# Logic_Engine_-_AVR.net
KiCad netlist of a schematic drawn in EAGLE
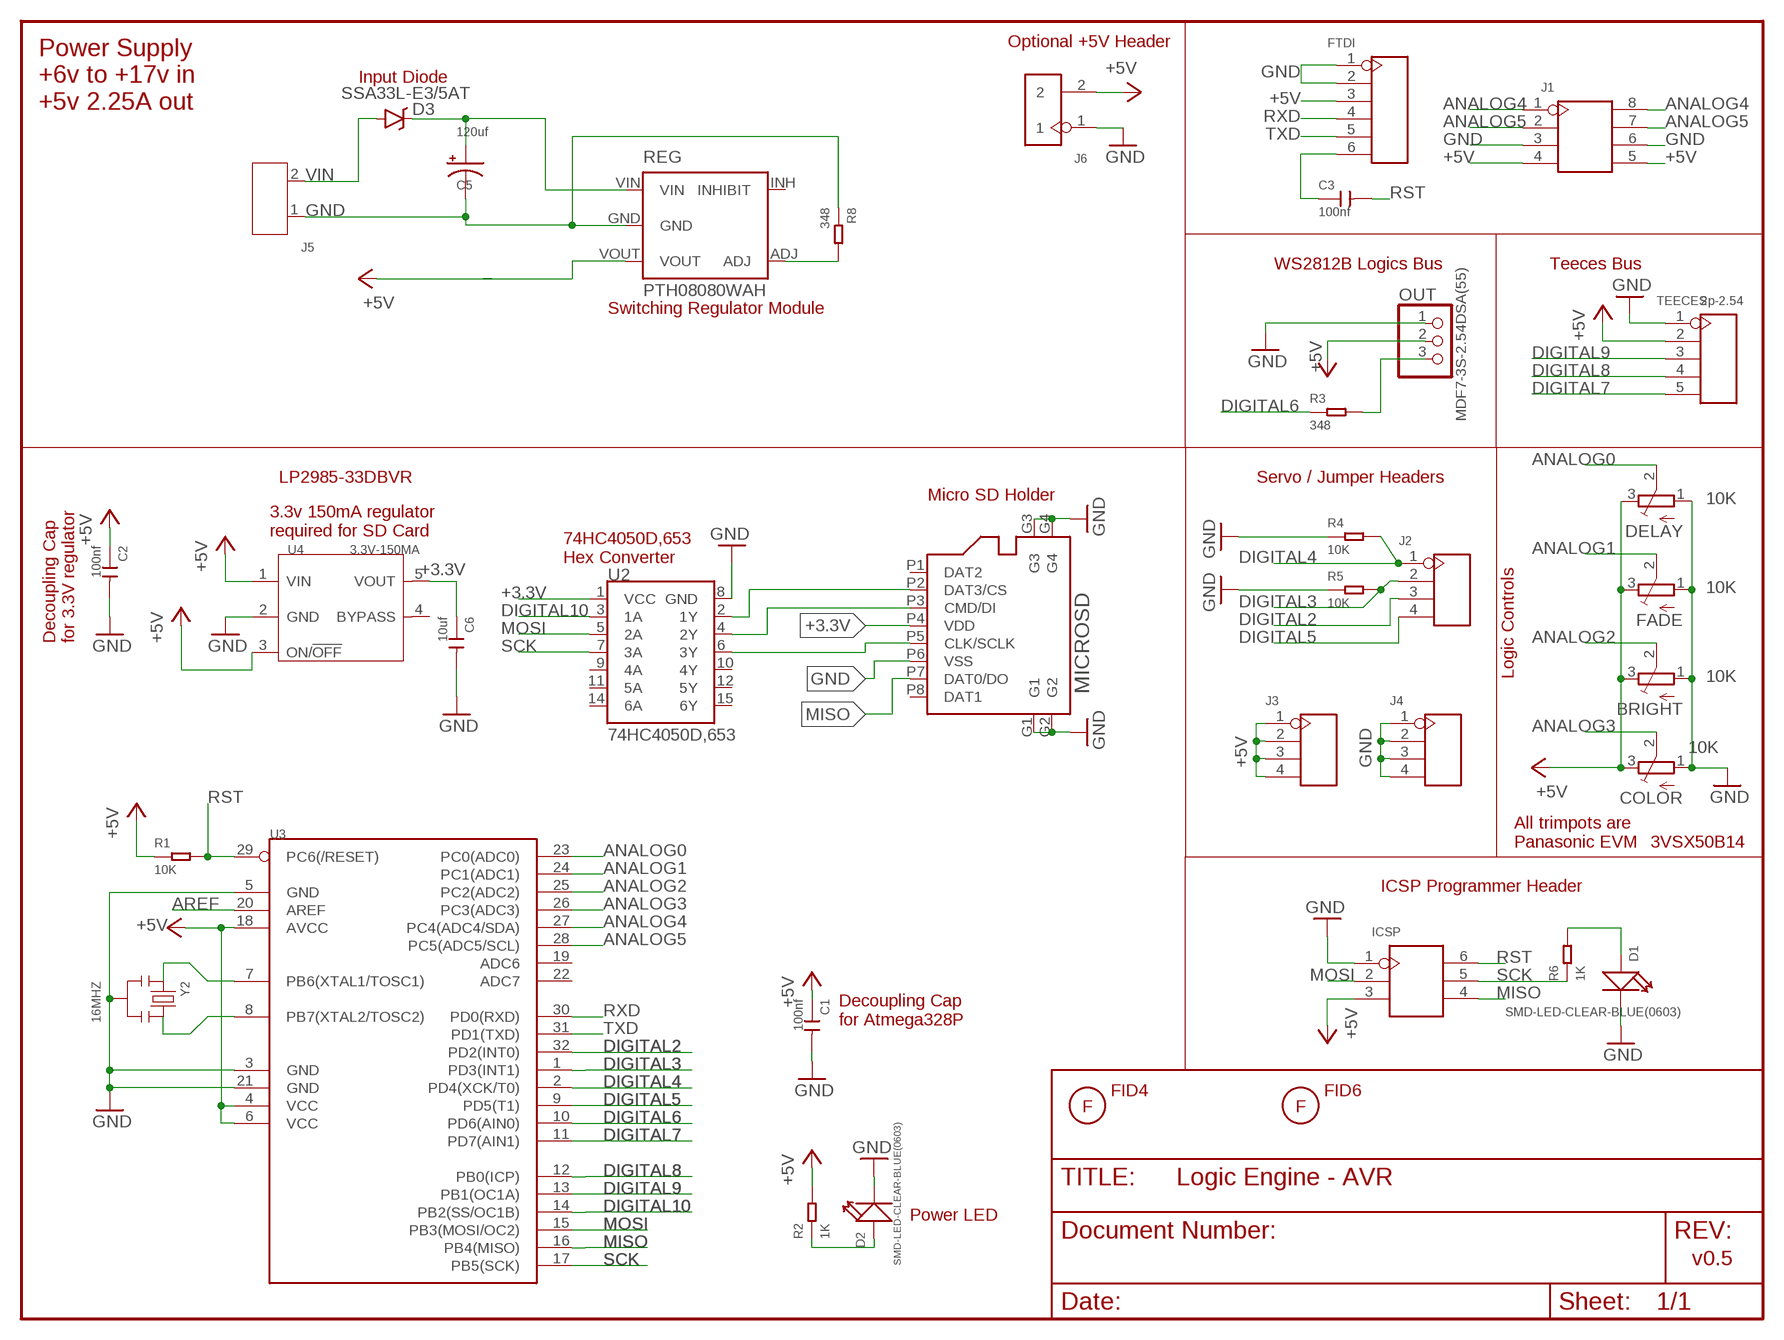
[diagram p0: schematic, sheet 1]

(export (version "E")
  (design (tool "Eeschema 10.0.6"))
  (components
    (comp (ref "BRIGHT")
      (value "10K")
      (footprint "eagle-import:EVM3V")
      (libsource (lib "eagle-import") (part "TRIMPOTEVM3V"))
    )
    (comp (ref "C1")
      (value "100nf")
      (footprint "eagle-import:C0805")
      (fields (field (name "MPN") "CC0805KRX7R9BB104"))
      (libsource (lib "eagle-import") (part "CERAMIC-100NF-50V-10%-X7R(0805)"))
    )
    (comp (ref "C2")
      (value "100nf")
      (footprint "eagle-import:C0805")
      (fields (field (name "MPN") "CC0805KRX7R9BB104"))
      (libsource (lib "eagle-import") (part "CERAMIC-100NF-50V-10%-X7R(0805)"))
    )
    (comp (ref "C3")
      (value "100nf")
      (footprint "eagle-import:C0805")
      (fields (field (name "MPN") "CC0805KRX7R9BB104"))
      (libsource (lib "eagle-import") (part "CERAMIC-100NF-50V-10%-X7R(0805)"))
    )
    (comp (ref "C5")
      (value "120uf")
      (footprint "eagle-import:PANASONIC_D")
      (libsource (lib "eagle-import") (part "CPOL-USD"))
    )
    (comp (ref "C6")
      (value "10uf")
      (footprint "eagle-import:C0805")
      (fields (field (name "MPN") "CC0805KKX5R8BB106"))
      (libsource (lib "eagle-import") (part "CERAMIC-10UF-25V-10%-X5R(0805)"))
    )
    (comp (ref "COLOR")
      (value "10K")
      (footprint "eagle-import:EVM3V")
      (libsource (lib "eagle-import") (part "TRIMPOTEVM3V"))
    )
    (comp (ref "D1")
      (value "SMD-LED-CLEAR-BLUE(0603)")
      (footprint "eagle-import:LED-0603")
      (fields (field (name "MPN") "19-217-BHC-ZL1M2RY-3T"))
      (libsource (lib "eagle-import") (part "SMD-LED-CLEAR-BLUE(0603)"))
    )
    (comp (ref "D2")
      (value "SMD-LED-CLEAR-BLUE(0603)")
      (footprint "eagle-import:LED-0603")
      (fields (field (name "MPN") "19-217-BHC-ZL1M2RY-3T"))
      (libsource (lib "eagle-import") (part "SMD-LED-CLEAR-BLUE(0603)"))
    )
    (comp (ref "D3")
      (value "SSA33L-E3/5AT")
      (footprint "eagle-import:SMA-DIODE")
      (libsource (lib "eagle-import") (part "B340A"))
    )
    (comp (ref "DELAY")
      (value "10K")
      (footprint "eagle-import:EVM3V")
      (libsource (lib "eagle-import") (part "TRIMPOTEVM3V"))
    )
    (comp (ref "FADE")
      (value "10K")
      (footprint "eagle-import:EVM3V")
      (libsource (lib "eagle-import") (part "TRIMPOTEVM3V"))
    )
    (comp (ref "FID4")
      (value "FIDUCIAL")
      (footprint "eagle-import:FIDUCIAL_G15")
      (libsource (lib "eagle-import") (part "FIDUCIAL"))
    )
    (comp (ref "FID6")
      (value "FIDUCIAL")
      (footprint "eagle-import:FIDUCIAL_G15")
      (libsource (lib "eagle-import") (part "FIDUCIAL"))
    )
    (comp (ref "FTDI")
      (value "DIP-BLACK-MALE-HEADER(6P-2.54)")
      (footprint "eagle-import:H6-2.54")
      (fields (field (name "MPN") "P125-1106A1BS116A1"))
      (libsource (lib "eagle-import") (part "DIP-BLACK-MALE-HEADER(6P-2.54)"))
    )
    (comp (ref "ICSP")
      (value "DIP-BLACK-MALE-HEADER(2X3P-2.54）-2.54")
      (footprint "eagle-import:H2X3-2.54")
      (fields (field (name "MPN") "P125-12A1BS116A1"))
      (libsource (lib "eagle-import") (part "DIP-BLACK-MALE-HEADER(2X3P-2.54）-2.54"))
    )
    (comp (ref "J1")
      (value "DIP-BLACK-MALE-HEADER-VERT(2X4P-2.54)")
      (footprint "eagle-import:H2X4-2.54")
      (fields (field (name "MPN") "P125-1208A0BS116A2"))
      (libsource (lib "eagle-import") (part "DIP-BLACK-MALE-HEADER-VERT(2X4P-2.54)"))
    )
    (comp (ref "J2")
      (value "DIP-BLACK-MALE-HEADER-VERT(4P-2.54)")
      (footprint "eagle-import:H4-2.54")
      (fields (field (name "MPN") "P125-1104A0BS116A1"))
      (libsource (lib "eagle-import") (part "DIP-BLACK-MALE-HEADER-VERT(4P-2.54)"))
    )
    (comp (ref "J3")
      (value "DIP-BLACK-MALE-HEADER-VERT(4P-2.54)")
      (footprint "eagle-import:H4-2.54")
      (fields (field (name "MPN") "P125-1104A0BS116A1"))
      (libsource (lib "eagle-import") (part "DIP-BLACK-MALE-HEADER-VERT(4P-2.54)"))
    )
    (comp (ref "J4")
      (value "DIP-BLACK-MALE-HEADER-VERT(4P-2.54)")
      (footprint "eagle-import:H4-2.54")
      (fields (field (name "MPN") "P125-1104A0BS116A1"))
      (libsource (lib "eagle-import") (part "DIP-BLACK-MALE-HEADER-VERT(4P-2.54)"))
    )
    (comp (ref "J5")
      (value "SCREW-TERMINAL-GREEN(2P-3.5)")
      (footprint "eagle-import:H2-3.5-7.0X7.0MM")
      (libsource (lib "eagle-import") (part "SCREW-TERMINAL-GREEN(2P-3.5)"))
    )
    (comp (ref "J6")
      (value "DIP-BLACK-MALE-HEADER-VERT(2P-2.54)")
      (footprint "eagle-import:H2-2.54")
      (fields (field (name "MPN") "P125-1102A0BS116A1"))
      (libsource (lib "eagle-import") (part "DIP-BLACK-MALE-HEADER-VERT(2P-2.54)"))
    )
    (comp (ref "MICROSD")
      (value "MICROSD47579-001")
      (footprint "eagle-import:SD-47579-001")
      (libsource (lib "eagle-import") (part "MICROSD47579-001"))
    )
    (comp (ref "OUT")
      (value "MDF7-3S-2.54DSA(55)")
      (footprint "eagle-import:MDF7_1X03")
      (libsource (lib "eagle-import") (part "MDF7-1X3"))
    )
    (comp (ref "R1")
      (value "10K")
      (footprint "eagle-import:R0603")
      (libsource (lib "eagle-import") (part "RES-0603"))
    )
    (comp (ref "R2")
      (value "1K")
      (footprint "eagle-import:R0603")
      (libsource (lib "eagle-import") (part "RES-0603"))
    )
    (comp (ref "R3")
      (value "348")
      (footprint "eagle-import:R0603")
      (libsource (lib "eagle-import") (part "Seeed-OPL-Resistor_RES-0603"))
    )
    (comp (ref "R4")
      (value "10K")
      (footprint "eagle-import:R0603")
      (libsource (lib "eagle-import") (part "RES-0603"))
    )
    (comp (ref "R5")
      (value "10K")
      (footprint "eagle-import:R0603")
      (libsource (lib "eagle-import") (part "RES-0603"))
    )
    (comp (ref "R6")
      (value "1K")
      (footprint "eagle-import:R0603")
      (libsource (lib "eagle-import") (part "RES-0603"))
    )
    (comp (ref "R8")
      (value "348")
      (footprint "eagle-import:R0603")
      (libsource (lib "eagle-import") (part "Seeed-OPL-Resistor_RES-0603"))
    )
    (comp (ref "REG")
      (value "PTH08080WAH")
      (footprint "eagle-import:PTH08080W_TH")
      (libsource (lib "eagle-import") (part "PTH08080WPTH08080W_TH"))
    )
    (comp (ref "TEECES")
      (value "2p-2.54")
      (footprint "eagle-import:H5-2.54")
      (libsource (lib "eagle-import") (part "DIP-BLACK-MALE-HEADER-VERT(5P-2.54)"))
    )
    (comp (ref "U2")
      (value "74HC4050D,653")
      (footprint "eagle-import:SO016")
      (libsource (lib "eagle-import") (part "HEX_CONVERTER"))
    )
    (comp (ref "U3")
      (value "MCU-ATMEGA328P-AU(TQFP32)")
      (footprint "eagle-import:TQFP32-0.8-7X7MM")
      (fields (field (name "MPN") "ATMEGA328P-AU"))
      (libsource (lib "eagle-import") (part "MCU-ATMEGA328P-AU(TQFP32)"))
    )
    (comp (ref "U4")
      (value "3.3V-150MA")
      (footprint "eagle-import:SOT-23-5")
      (fields (field (name "MPN") "LP2985-50DBVR") (field (name "MPN_1") "LP2985-33DBVR"))
      (libsource (lib "eagle-import") (part "PMIC-LP2985-50DBVR(SOT23-5)"))
    )
    (comp (ref "Y2")
      (value "16MHZ")
      (footprint "eagle-import:X3-SMD-3.6X1.3X0.8MM")
      (fields (field (name "MPN") "CSTCE16M0V53-R0"))
      (libsource (lib "eagle-import") (part "SMD-RESONATOR-16MHZ-15PF-0.5%-40R(3P-3.2X1.3MM)"))
    )
  )
  (nets
    (net (code "1") (name "+3.3V") (class "Default")
      (node (ref "C6") (pin "1") (pinfunction "1_1") (pintype "passive"))
      (node (ref "MICROSD") (pin "P4") (pinfunction "VDD_P4") (pintype "power_in"))
      (node (ref "U2") (pin "1") (pinfunction "VCC_1") (pintype "bidirectional"))
      (node (ref "U4") (pin "5") (pinfunction "VOUT_5") (pintype "bidirectional"))
    )
    (net (code "2") (name "+5V") (class "Default")
      (node (ref "BRIGHT") (pin "3") (pinfunction "E_3") (pintype "passive"))
      (node (ref "C1") (pin "1") (pinfunction "1_1") (pintype "passive"))
      (node (ref "C2") (pin "1") (pinfunction "1_1") (pintype "passive"))
      (node (ref "COLOR") (pin "3") (pinfunction "E_3") (pintype "passive"))
      (node (ref "DELAY") (pin "3") (pinfunction "E_3") (pintype "passive"))
      (node (ref "FADE") (pin "3") (pinfunction "E_3") (pintype "passive"))
      (node (ref "FTDI") (pin "3") (pinfunction "3_3") (pintype "bidirectional"))
      (node (ref "ICSP") (pin "3") (pinfunction "3_3") (pintype "bidirectional"))
      (node (ref "J1") (pin "4") (pinfunction "4_4") (pintype "bidirectional"))
      (node (ref "J1") (pin "5") (pinfunction "5_5") (pintype "bidirectional"))
      (node (ref "J3") (pin "1") (pinfunction "P$1_1") (pintype "bidirectional"))
      (node (ref "J3") (pin "2") (pinfunction "P$2_2") (pintype "bidirectional"))
      (node (ref "J3") (pin "3") (pinfunction "P$3_3") (pintype "bidirectional"))
      (node (ref "J3") (pin "4") (pinfunction "P$4_4") (pintype "bidirectional"))
      (node (ref "J6") (pin "2") (pinfunction "2_2") (pintype "bidirectional"))
      (node (ref "OUT") (pin "2") (pinfunction "2_2") (pintype "passive"))
      (node (ref "R1") (pin "1") (pinfunction "1_1") (pintype "passive"))
      (node (ref "R2") (pin "2") (pinfunction "2_2") (pintype "passive"))
      (node (ref "REG") (pin "VOUT") (pinfunction "VOUT_VOUT") (pintype "output"))
      (node (ref "TEECES") (pin "2") (pinfunction "2_2") (pintype "bidirectional"))
      (node (ref "U3") (pin "18") (pinfunction "AVCC_18") (pintype "bidirectional"))
      (node (ref "U3") (pin "4") (pinfunction "VCC_4") (pintype "bidirectional"))
      (node (ref "U3") (pin "6") (pinfunction "VCC_6") (pintype "bidirectional"))
      (node (ref "U4") (pin "1") (pinfunction "VIN_1") (pintype "bidirectional"))
      (node (ref "U4") (pin "3") (pinfunction "ON/~{OFF}_3") (pintype "bidirectional"))
    )
    (net (code "3") (name "/ANALOG0") (class "Default")
      (node (ref "DELAY") (pin "2") (pinfunction "S_2") (pintype "passive"))
      (node (ref "U3") (pin "23") (pinfunction "PC0(ADC0)_23") (pintype "bidirectional"))
    )
    (net (code "4") (name "/ANALOG1") (class "Default")
      (node (ref "FADE") (pin "2") (pinfunction "S_2") (pintype "passive"))
      (node (ref "U3") (pin "24") (pinfunction "PC1(ADC1)_24") (pintype "bidirectional"))
    )
    (net (code "5") (name "/ANALOG2") (class "Default")
      (node (ref "BRIGHT") (pin "2") (pinfunction "S_2") (pintype "passive"))
      (node (ref "U3") (pin "25") (pinfunction "PC2(ADC2)_25") (pintype "bidirectional"))
    )
    (net (code "6") (name "/ANALOG3") (class "Default")
      (node (ref "COLOR") (pin "2") (pinfunction "S_2") (pintype "passive"))
      (node (ref "U3") (pin "26") (pinfunction "PC3(ADC3)_26") (pintype "bidirectional"))
    )
    (net (code "7") (name "/ANALOG4") (class "Default")
      (node (ref "J1") (pin "1") (pinfunction "1_1") (pintype "bidirectional"))
      (node (ref "J1") (pin "8") (pinfunction "8_8") (pintype "bidirectional"))
      (node (ref "U3") (pin "27") (pinfunction "PC4(ADC4/SDA)_27") (pintype "bidirectional"))
    )
    (net (code "8") (name "/ANALOG5") (class "Default")
      (node (ref "J1") (pin "2") (pinfunction "2_2") (pintype "bidirectional"))
      (node (ref "J1") (pin "7") (pinfunction "7_7") (pintype "bidirectional"))
      (node (ref "U3") (pin "28") (pinfunction "PC5(ADC5/SCL)_28") (pintype "bidirectional"))
    )
    (net (code "9") (name "/AREF") (class "Default")
      (node (ref "U3") (pin "20") (pinfunction "AREF_20") (pintype "bidirectional"))
    )
    (net (code "10") (name "/DIGITAL2") (class "Default")
      (node (ref "J2") (pin "3") (pinfunction "P$3_3") (pintype "bidirectional"))
      (node (ref "U3") (pin "32") (pinfunction "PD2(INT0)_32") (pintype "bidirectional"))
    )
    (net (code "11") (name "/DIGITAL3") (class "Default")
      (node (ref "J2") (pin "2") (pinfunction "P$2_2") (pintype "bidirectional"))
      (node (ref "R5") (pin "2") (pinfunction "2_2") (pintype "passive"))
      (node (ref "U3") (pin "1") (pinfunction "PD3(INT1)_1") (pintype "bidirectional"))
    )
    (net (code "12") (name "/DIGITAL4") (class "Default")
      (node (ref "J2") (pin "1") (pinfunction "P$1_1") (pintype "bidirectional"))
      (node (ref "R4") (pin "2") (pinfunction "2_2") (pintype "passive"))
      (node (ref "U3") (pin "2") (pinfunction "PD4(XCK/T0)_2") (pintype "bidirectional"))
    )
    (net (code "13") (name "/DIGITAL5") (class "Default")
      (node (ref "J2") (pin "4") (pinfunction "P$4_4") (pintype "bidirectional"))
      (node (ref "U3") (pin "9") (pinfunction "PD5(T1)_9") (pintype "bidirectional"))
    )
    (net (code "14") (name "/DIGITAL6") (class "Default")
      (node (ref "R3") (pin "1") (pinfunction "1_1") (pintype "passive"))
      (node (ref "U3") (pin "10") (pinfunction "PD6(AIN0)_10") (pintype "bidirectional"))
    )
    (net (code "15") (name "/DIGITAL7") (class "Default")
      (node (ref "TEECES") (pin "5") (pinfunction "5_5") (pintype "bidirectional"))
      (node (ref "U3") (pin "11") (pinfunction "PD7(AIN1)_11") (pintype "bidirectional"))
    )
    (net (code "16") (name "/DIGITAL8") (class "Default")
      (node (ref "TEECES") (pin "4") (pinfunction "4_4") (pintype "bidirectional"))
      (node (ref "U3") (pin "12") (pinfunction "PB0(ICP)_12") (pintype "bidirectional"))
    )
    (net (code "17") (name "/DIGITAL9") (class "Default")
      (node (ref "TEECES") (pin "3") (pinfunction "3_3") (pintype "bidirectional"))
      (node (ref "U3") (pin "13") (pinfunction "PB1(OC1A)_13") (pintype "bidirectional"))
    )
    (net (code "18") (name "/DIGITAL10") (class "Default")
      (node (ref "U2") (pin "3") (pinfunction "1A_3") (pintype "bidirectional"))
      (node (ref "U3") (pin "14") (pinfunction "PB2(SS/OC1B)_14") (pintype "bidirectional"))
    )
    (net (code "19") (name "/MOSI") (class "Default")
      (node (ref "ICSP") (pin "2") (pinfunction "2_2") (pintype "bidirectional"))
      (node (ref "U2") (pin "5") (pinfunction "2A_5") (pintype "bidirectional"))
      (node (ref "U3") (pin "15") (pinfunction "PB3(MOSI/OC2)_15") (pintype "bidirectional"))
    )
    (net (code "20") (name "/RST") (class "Default")
      (node (ref "C3") (pin "2") (pinfunction "2_2") (pintype "passive"))
      (node (ref "ICSP") (pin "6") (pinfunction "6_6") (pintype "bidirectional"))
      (node (ref "R1") (pin "2") (pinfunction "2_2") (pintype "passive"))
      (node (ref "U3") (pin "29") (pinfunction "PC6(/RESET)_29") (pintype "bidirectional"))
    )
    (net (code "21") (name "/RXD") (class "Default")
      (node (ref "FTDI") (pin "4") (pinfunction "4_4") (pintype "bidirectional"))
      (node (ref "U3") (pin "30") (pinfunction "PD0(RXD)_30") (pintype "bidirectional"))
    )
    (net (code "22") (name "/SCK") (class "Default")
      (node (ref "ICSP") (pin "5") (pinfunction "5_5") (pintype "bidirectional"))
      (node (ref "R6") (pin "1") (pinfunction "1_1") (pintype "passive"))
      (node (ref "U2") (pin "7") (pinfunction "3A_7") (pintype "bidirectional"))
      (node (ref "U3") (pin "17") (pinfunction "PB5(SCK)_17") (pintype "bidirectional"))
    )
    (net (code "23") (name "/TXD") (class "Default")
      (node (ref "FTDI") (pin "5") (pinfunction "5_5") (pintype "bidirectional"))
      (node (ref "U3") (pin "31") (pinfunction "PD1(TXD)_31") (pintype "bidirectional"))
    )
    (net (code "24") (name "/VIN") (class "Default")
      (node (ref "D3") (pin "A") (pinfunction "A_A") (pintype "passive"))
      (node (ref "J5") (pin "2") (pinfunction "2_2") (pintype "bidirectional"))
    )
    (net (code "25") (name "GND") (class "Default")
      (node (ref "BRIGHT") (pin "1") (pinfunction "A_1") (pintype "passive"))
      (node (ref "C1") (pin "2") (pinfunction "2_2") (pintype "passive"))
      (node (ref "C2") (pin "2") (pinfunction "2_2") (pintype "passive"))
      (node (ref "C5") (pin "-") (pinfunction "-_-") (pintype "passive"))
      (node (ref "C6") (pin "2") (pinfunction "2_2") (pintype "passive"))
      (node (ref "COLOR") (pin "1") (pinfunction "A_1") (pintype "passive"))
      (node (ref "D1") (pin "-") (pinfunction "-_-") (pintype "passive"))
      (node (ref "D2") (pin "-") (pinfunction "-_-") (pintype "passive"))
      (node (ref "DELAY") (pin "1") (pinfunction "A_1") (pintype "passive"))
      (node (ref "FADE") (pin "1") (pinfunction "A_1") (pintype "passive"))
      (node (ref "FTDI") (pin "1") (pinfunction "1_1") (pintype "bidirectional"))
      (node (ref "FTDI") (pin "2") (pinfunction "2_2") (pintype "bidirectional"))
      (node (ref "ICSP") (pin "1") (pinfunction "1_1") (pintype "bidirectional"))
      (node (ref "J1") (pin "3") (pinfunction "3_3") (pintype "bidirectional"))
      (node (ref "J1") (pin "6") (pinfunction "6_6") (pintype "bidirectional"))
      (node (ref "J4") (pin "1") (pinfunction "P$1_1") (pintype "bidirectional"))
      (node (ref "J4") (pin "2") (pinfunction "P$2_2") (pintype "bidirectional"))
      (node (ref "J4") (pin "3") (pinfunction "P$3_3") (pintype "bidirectional"))
      (node (ref "J4") (pin "4") (pinfunction "P$4_4") (pintype "bidirectional"))
      (node (ref "J5") (pin "1") (pinfunction "1_1") (pintype "bidirectional"))
      (node (ref "J6") (pin "1") (pinfunction "1_1") (pintype "bidirectional"))
      (node (ref "MICROSD") (pin "G1") (pinfunction "G1_G1") (pintype "power_in"))
      (node (ref "MICROSD") (pin "G2") (pinfunction "G2_G2") (pintype "power_in"))
      (node (ref "MICROSD") (pin "G3") (pinfunction "G3_G3") (pintype "passive"))
      (node (ref "MICROSD") (pin "G4") (pinfunction "G4_G4") (pintype "passive"))
      (node (ref "MICROSD") (pin "P6") (pinfunction "VSS_P6") (pintype "power_in"))
      (node (ref "OUT") (pin "1") (pinfunction "1_1") (pintype "passive"))
      (node (ref "R4") (pin "1") (pinfunction "1_1") (pintype "passive"))
      (node (ref "R5") (pin "1") (pinfunction "1_1") (pintype "passive"))
      (node (ref "R8") (pin "1") (pinfunction "1_1") (pintype "passive"))
      (node (ref "REG") (pin "GND") (pinfunction "GND_GND") (pintype "power_in"))
      (node (ref "TEECES") (pin "1") (pinfunction "1_1") (pintype "bidirectional"))
      (node (ref "U2") (pin "8") (pinfunction "GND_8") (pintype "bidirectional"))
      (node (ref "U3") (pin "21") (pinfunction "GND_21") (pintype "bidirectional"))
      (node (ref "U3") (pin "3") (pinfunction "GND_3") (pintype "bidirectional"))
      (node (ref "U3") (pin "5") (pinfunction "GND_5") (pintype "bidirectional"))
      (node (ref "U4") (pin "2") (pinfunction "GND_2") (pintype "bidirectional"))
      (node (ref "Y2") (pin "2") (pinfunction "2_2") (pintype "passive"))
    )
    (net (code "26") (name "MISO") (class "Default")
      (node (ref "ICSP") (pin "4") (pinfunction "4_4") (pintype "bidirectional"))
      (node (ref "MICROSD") (pin "P7") (pinfunction "DAT0/DO_P7") (pintype "output"))
      (node (ref "U3") (pin "16") (pinfunction "PB4(MISO)_16") (pintype "bidirectional"))
    )
    (net (code "27") (name "Net-(C3-Pad1)") (class "Default")
      (node (ref "C3") (pin "1") (pinfunction "1_1") (pintype "passive"))
      (node (ref "FTDI") (pin "6") (pinfunction "6_6") (pintype "bidirectional"))
    )
    (net (code "28") (name "Net-(C5-Pad+)") (class "Default")
      (node (ref "C5") (pin "+") (pinfunction "+_+") (pintype "passive"))
      (node (ref "D3") (pin "C") (pinfunction "C_C") (pintype "passive"))
      (node (ref "REG") (pin "VIN") (pinfunction "VIN_VIN") (pintype "input"))
    )
    (net (code "29") (name "Net-(D1-Pad+)") (class "Default")
      (node (ref "D1") (pin "+") (pinfunction "+_+") (pintype "passive"))
      (node (ref "R6") (pin "2") (pinfunction "2_2") (pintype "passive"))
    )
    (net (code "30") (name "Net-(D2-Pad+)") (class "Default")
      (node (ref "D2") (pin "+") (pinfunction "+_+") (pintype "passive"))
      (node (ref "R2") (pin "1") (pinfunction "1_1") (pintype "passive"))
    )
    (net (code "31") (name "Net-(MICROSD-CLK{slash}SCLK)") (class "Default")
      (node (ref "MICROSD") (pin "P5") (pinfunction "CLK/SCLK_P5") (pintype "input"))
      (node (ref "U2") (pin "6") (pinfunction "3Y_6") (pintype "bidirectional"))
    )
    (net (code "32") (name "Net-(MICROSD-CMD{slash}DI)") (class "Default")
      (node (ref "MICROSD") (pin "P3") (pinfunction "CMD/DI_P3") (pintype "input"))
      (node (ref "U2") (pin "4") (pinfunction "2Y_4") (pintype "bidirectional"))
    )
    (net (code "33") (name "Net-(MICROSD-DAT3{slash}CS)") (class "Default")
      (node (ref "MICROSD") (pin "P2") (pinfunction "DAT3/CS_P2") (pintype "input"))
      (node (ref "U2") (pin "2") (pinfunction "1Y_2") (pintype "bidirectional"))
    )
    (net (code "34") (name "Net-(OUT-Pad3)") (class "Default")
      (node (ref "OUT") (pin "3") (pinfunction "3_3") (pintype "passive"))
      (node (ref "R3") (pin "2") (pinfunction "2_2") (pintype "passive"))
    )
    (net (code "35") (name "Net-(R8-Pad2)") (class "Default")
      (node (ref "R8") (pin "2") (pinfunction "2_2") (pintype "passive"))
      (node (ref "REG") (pin "ADJ") (pinfunction "ADJ_ADJ") (pintype "input"))
    )
    (net (code "36") (name "Net-(U3-PB6(XTAL1{slash}TOSC1))") (class "Default")
      (node (ref "U3") (pin "7") (pinfunction "PB6(XTAL1/TOSC1)_7") (pintype "bidirectional"))
      (node (ref "Y2") (pin "1") (pinfunction "1_1") (pintype "passive"))
    )
    (net (code "37") (name "Net-(U3-PB7(XTAL2{slash}TOSC2))") (class "Default")
      (node (ref "U3") (pin "8") (pinfunction "PB7(XTAL2/TOSC2)_8") (pintype "bidirectional"))
      (node (ref "Y2") (pin "3") (pinfunction "3_3") (pintype "passive"))
    )
    (net (code "38") (name "unconnected-(MICROSD-DAT1-PadP8)") (class "Default")
      (node (ref "MICROSD") (pin "P8") (pinfunction "DAT1_P8") (pintype "bidirectional"))
    )
    (net (code "39") (name "unconnected-(MICROSD-DAT2-PadP1)") (class "Default")
      (node (ref "MICROSD") (pin "P1") (pinfunction "DAT2_P1") (pintype "bidirectional"))
    )
    (net (code "40") (name "unconnected-(REG-INHIBIT-PadINH)") (class "Default")
      (node (ref "REG") (pin "INH") (pinfunction "INHIBIT_INH") (pintype "input"))
    )
    (net (code "41") (name "unconnected-(U2-4A-Pad9)") (class "Default")
      (node (ref "U2") (pin "9") (pinfunction "4A_9") (pintype "bidirectional"))
    )
    (net (code "42") (name "unconnected-(U2-4Y-Pad10)") (class "Default")
      (node (ref "U2") (pin "10") (pinfunction "4Y_10") (pintype "bidirectional"))
    )
    (net (code "43") (name "unconnected-(U2-5A-Pad11)") (class "Default")
      (node (ref "U2") (pin "11") (pinfunction "5A_11") (pintype "bidirectional"))
    )
    (net (code "44") (name "unconnected-(U2-5Y-Pad12)") (class "Default")
      (node (ref "U2") (pin "12") (pinfunction "5Y_12") (pintype "bidirectional"))
    )
    (net (code "45") (name "unconnected-(U2-6A-Pad14)") (class "Default")
      (node (ref "U2") (pin "14") (pinfunction "6A_14") (pintype "bidirectional"))
    )
    (net (code "46") (name "unconnected-(U2-6Y-Pad15)") (class "Default")
      (node (ref "U2") (pin "15") (pinfunction "6Y_15") (pintype "bidirectional"))
    )
    (net (code "47") (name "unconnected-(U3-ADC6-Pad19)") (class "Default")
      (node (ref "U3") (pin "19") (pinfunction "ADC6_19") (pintype "bidirectional"))
    )
    (net (code "48") (name "unconnected-(U3-ADC7-Pad22)") (class "Default")
      (node (ref "U3") (pin "22") (pinfunction "ADC7_22") (pintype "bidirectional"))
    )
    (net (code "49") (name "unconnected-(U4-BYPASS-Pad4)") (class "Default")
      (node (ref "U4") (pin "4") (pinfunction "BYPASS_4") (pintype "bidirectional"))
    )
  )
)
